# RelayModuleTest.net
KiCad netlist of a schematic drawn in EAGLE
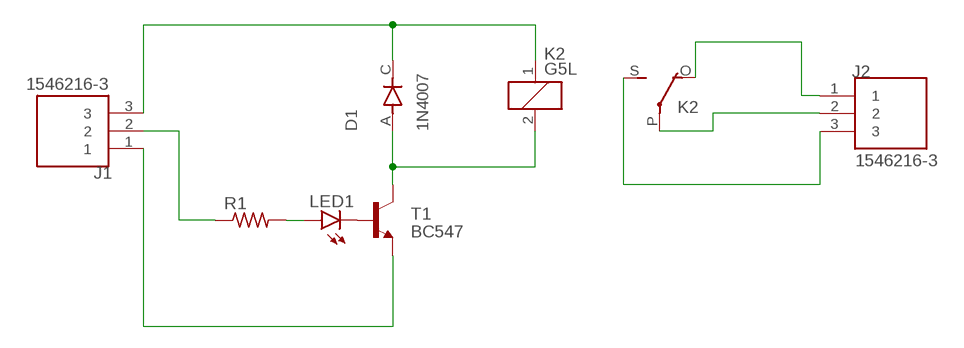
[diagram p0: schematic, sheet 1]

(export (version "E")
  (design (tool "Eeschema 10.0.6"))
  (components
    (comp (ref "D1")
      (value "1N4007")
      (footprint "eagle-import:DIOAD1060W80L520D270")
      (fields (field (name "MF") "ON Semiconductor"))
      (libsource (lib "eagle-import") (part "1N4007"))
    )
    (comp (ref "J1")
      (value "1546216-3")
      (footprint "eagle-import:TE_1546216-3")
      (fields (field (name "MF") "TE Connectivity"))
      (libsource (lib "eagle-import") (part "1546216-3"))
    )
    (comp (ref "J2")
      (value "1546216-3")
      (footprint "eagle-import:TE_1546216-3")
      (fields (field (name "MF") "TE Connectivity"))
      (libsource (lib "eagle-import") (part "1546216-3"))
    )
    (comp (ref "K2")
      (value "G5L")
      (footprint "eagle-import:G5LE")
      (libsource (lib "eagle-import") (part "G5L"))
    )
    (comp (ref "LED1")
      (value "LED3MM")
      (footprint "eagle-import:LED3MM")
      (libsource (lib "eagle-import") (part "LED3MM"))
    )
    (comp (ref "R1")
      (value "R-US_0207/15")
      (footprint "eagle-import:0207_15")
      (libsource (lib "eagle-import") (part "R-US_0207/15"))
    )
    (comp (ref "T1")
      (value "BC547")
      (footprint "eagle-import:TO92")
      (fields (field (name "MF") "ON"))
      (libsource (lib "eagle-import") (part "BC547"))
    )
  )
  (nets
    (net (code "1") (name "Net-(D1-PadC)") (class "Default")
      (node (ref "D1") (pin "C") (pinfunction "C_C") (pintype "passive"))
      (node (ref "J1") (pin "3") (pinfunction "3_3") (pintype "passive"))
      (node (ref "K2") (pin "1") (pinfunction "1_1") (pintype "passive"))
    )
    (net (code "2") (name "Net-(J1-Pad2)") (class "Default")
      (node (ref "J1") (pin "2") (pinfunction "2_2") (pintype "passive"))
      (node (ref "R1") (pin "1") (pinfunction "1_1") (pintype "passive"))
    )
    (net (code "3") (name "Net-(J2-Pad1)") (class "Default")
      (node (ref "J2") (pin "1") (pinfunction "1_1") (pintype "passive"))
      (node (ref "K2") (pin "O") (pinfunction "O_O") (pintype "passive"))
    )
    (net (code "4") (name "Net-(J2-Pad2)") (class "Default")
      (node (ref "J2") (pin "2") (pinfunction "2_2") (pintype "passive"))
      (node (ref "K2") (pin "P") (pinfunction "P_P") (pintype "passive"))
    )
    (net (code "5") (name "Net-(J2-Pad3)") (class "Default")
      (node (ref "J2") (pin "3") (pinfunction "3_3") (pintype "passive"))
      (node (ref "K2") (pin "S") (pinfunction "S_S") (pintype "passive"))
    )
    (net (code "6") (name "Net-(LED1-C)") (class "Default")
      (node (ref "LED1") (pin "K") (pinfunction "C_K") (pintype "passive"))
      (node (ref "T1") (pin "2") (pinfunction "B_2") (pintype "passive"))
    )
    (net (code "7") (name "Net-(LED1-PadA)") (class "Default")
      (node (ref "LED1") (pin "A") (pinfunction "A_A") (pintype "passive"))
      (node (ref "R1") (pin "2") (pinfunction "2_2") (pintype "passive"))
    )
    (net (code "8") (name "Net-(T1-C)") (class "Default")
      (node (ref "D1") (pin "A") (pinfunction "A_A") (pintype "passive"))
      (node (ref "K2") (pin "2") (pinfunction "2_2") (pintype "passive"))
      (node (ref "T1") (pin "3") (pinfunction "C_3") (pintype "passive"))
    )
    (net (code "9") (name "Net-(T1-E)") (class "Default")
      (node (ref "J1") (pin "1") (pinfunction "1_1") (pintype "passive"))
      (node (ref "T1") (pin "1") (pinfunction "E_1") (pintype "passive"))
    )
  )
)
